# 5G_1.net
KiCad netlist of a schematic drawn in Altium Designer
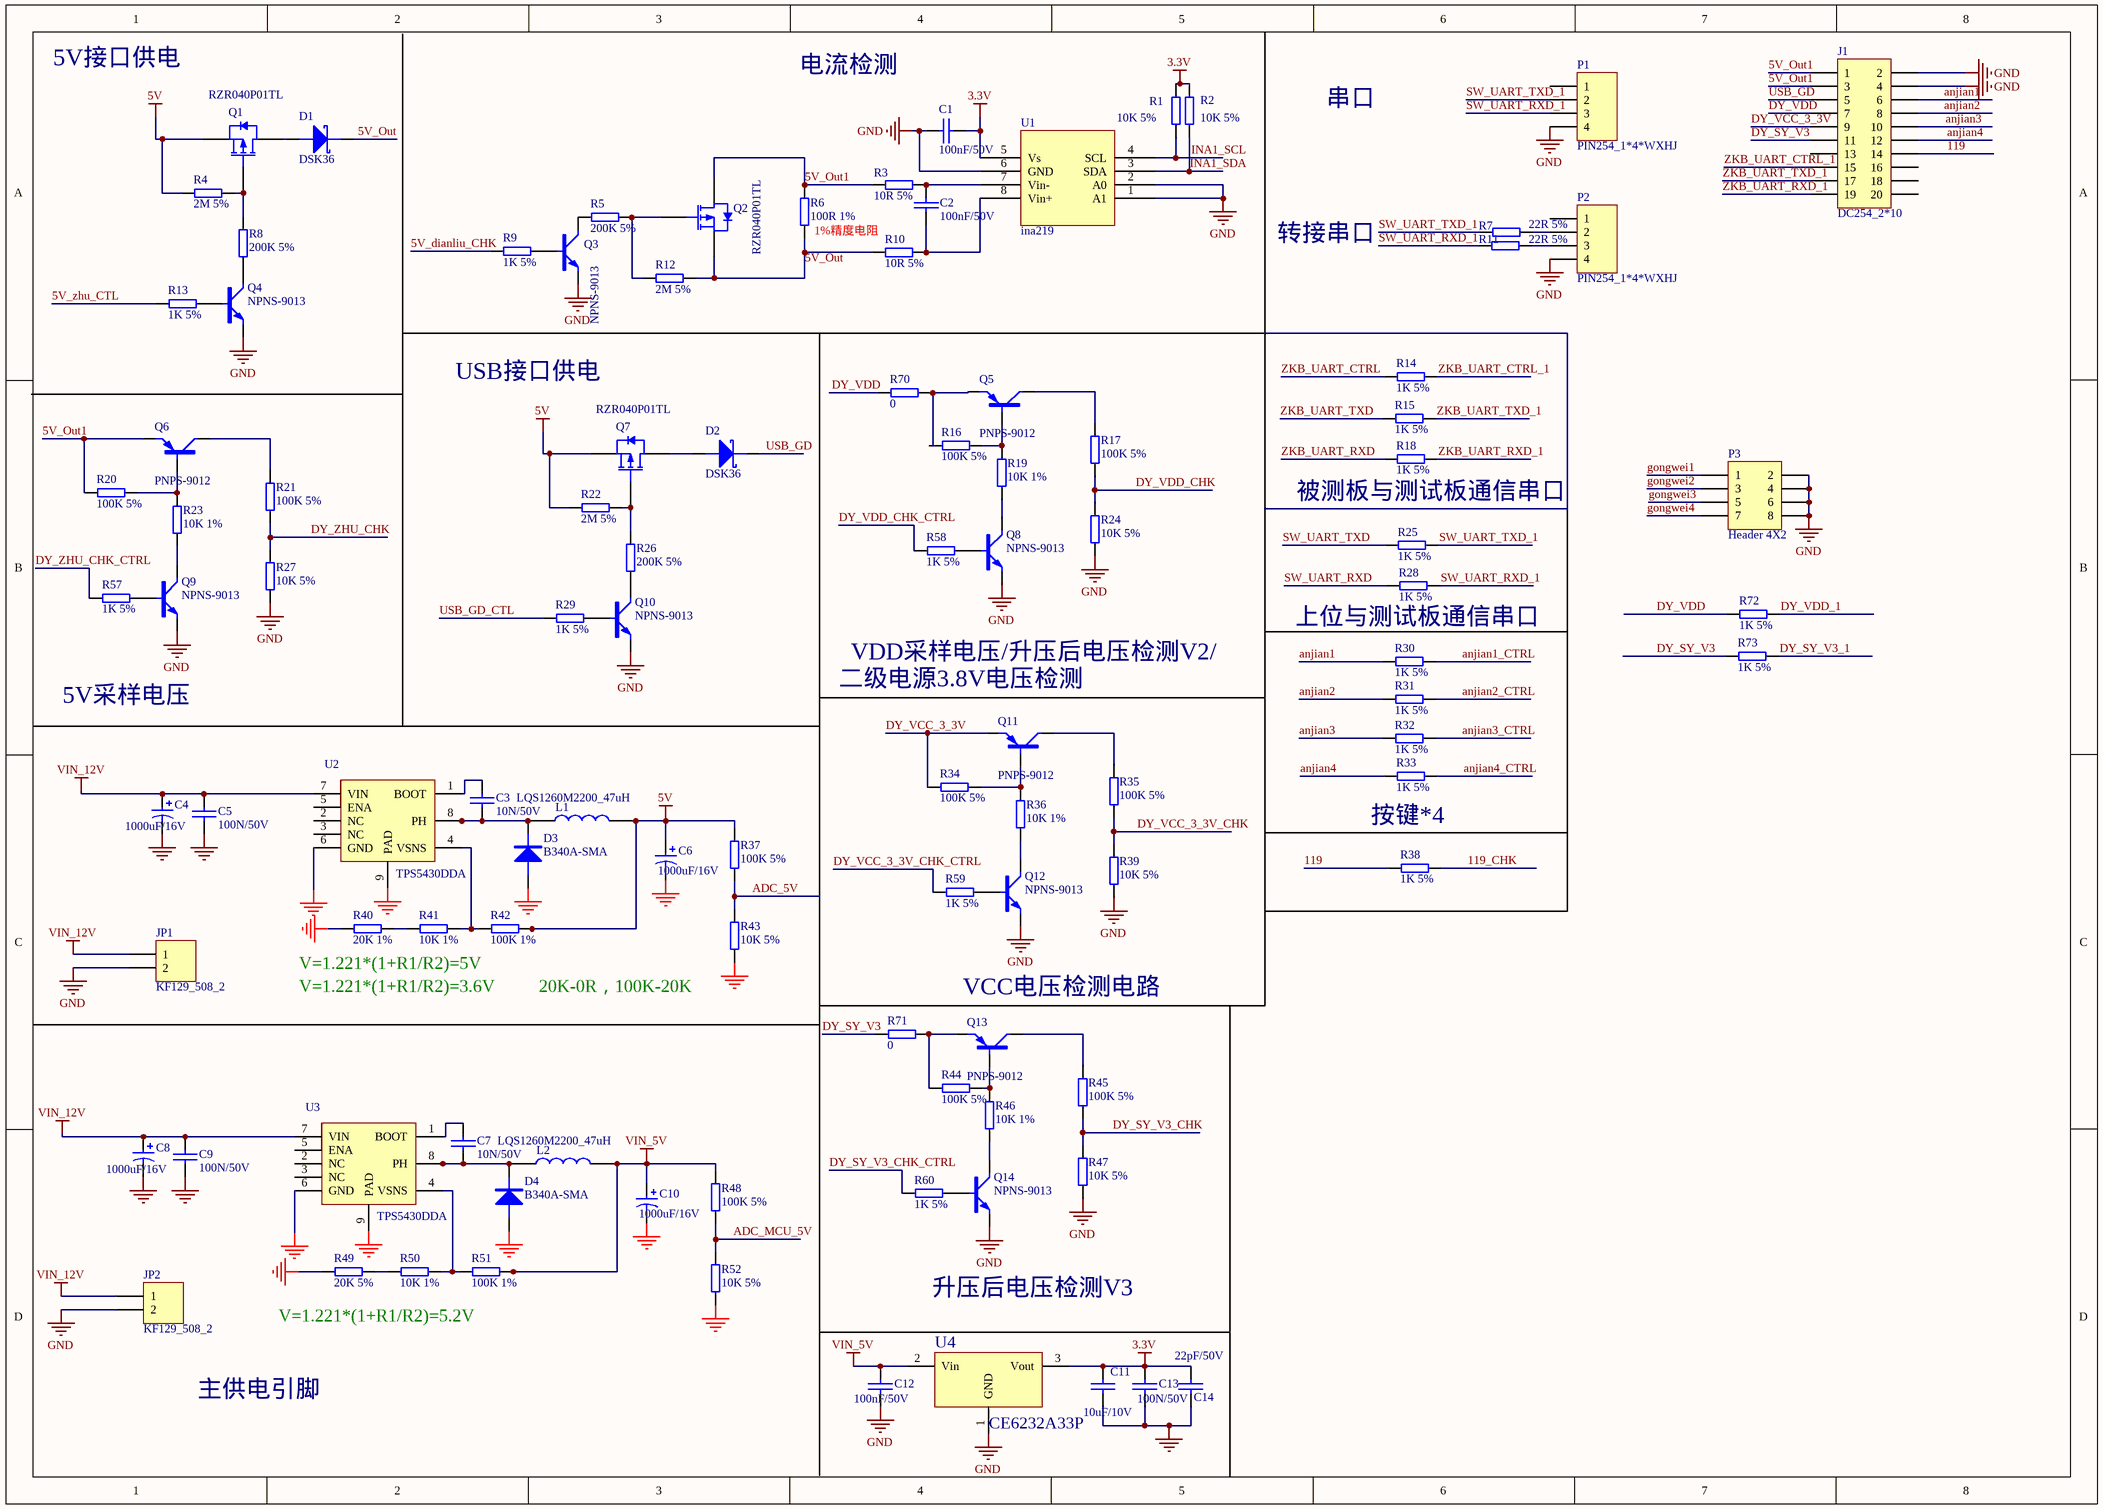
[diagram p0: 5G智慧网关工装1.SchDoc]

(export (version "E")
  (design (tool "Eeschema 10.0.6"))
  (components
    (comp (ref "C1")
      (value "100nF/50V")
      (footprint "CAP0603")
      (description "104pF,50 V,±10%,0603,国巨,CC0603KRX7R9BB104")
      (fields (field (name "PART NUMBER") "101020103-0021"))
      (libsource (lib "Database_Libs2") (part "CC03K7R9_100N"))
    )
    (comp (ref "C2")
      (value "100nF/50V")
      (footprint "CAP0603")
      (description "104pF,50 V,±10%,0603,国巨,CC0603KRX7R9BB104")
      (fields (field (name "PART NUMBER") "101020103-0021"))
      (libsource (lib "Database_Libs2") (part "CC03K7R9_100N"))
    )
    (comp (ref "C3")
      (value "10N/50V")
      (footprint "CAP0603")
      (description "10N/50V，±10%，0603")
      (fields (field (name "PART NUMBER") "101020103-0007"))
      (libsource (lib "Database_Libs1") (part "CC03K7R9B_10N"))
    )
    (comp (ref "C4")
      (value "1000uF/16V")
      (footprint "CAPPC_350_800_1600")
      (description "1000uF,16 V,±20%,8*20mm,Rubycon,16ZLH1000M")
      (fields (field (name "PART NUMBER") "1010203-0029"))
      (libsource (lib "Database_Libs2") (part "CAL7MRZLH_1000U_R"))
    )
    (comp (ref "C5")
      (value "100N/50V")
      (footprint "CAP0603")
      (description "100N/50V，±10%，0603")
      (fields (field (name "PART NUMBER") "101020103-0021"))
      (libsource (lib "Database_Libs1") (part "CC03K7R9B_100N"))
    )
    (comp (ref "C6")
      (value "1000uF/16V")
      (footprint "CAPPC_350_800_1600")
      (description "1000uF,16 V,±20%,8*20mm,Rubycon,16ZLH1000M")
      (fields (field (name "PART NUMBER") "1010203-0029"))
      (libsource (lib "Database_Libs2") (part "CAL7MRZLH_1000U_R"))
    )
    (comp (ref "C7")
      (value "10N/50V")
      (footprint "CAP0603")
      (description "10N/50V，±10%，0603")
      (fields (field (name "PART NUMBER") "101020103-0007"))
      (libsource (lib "Database_Libs1") (part "CC03K7R9B_10N"))
    )
    (comp (ref "C8")
      (value "1000uF/16V")
      (footprint "CAPPC_350_800_1600")
      (description "1000uF,16 V,±20%,8*20mm,Rubycon,16ZLH1000M")
      (fields (field (name "PART NUMBER") "1010203-0029"))
      (libsource (lib "Database_Libs2") (part "CAL7MRZLH_1000U_R"))
    )
    (comp (ref "C9")
      (value "100N/50V")
      (footprint "CAP0603")
      (description "100N/50V，±10%，0603")
      (fields (field (name "PART NUMBER") "101020103-0021"))
      (libsource (lib "Database_Libs1") (part "CC03K7R9B_100N"))
    )
    (comp (ref "C10")
      (value "1000uF/16V")
      (footprint "CAPPC_350_800_1600")
      (description "1000uF,16 V,±20%,8*20mm,Rubycon,16ZLH1000M")
      (fields (field (name "PART NUMBER") "1010203-0029"))
      (libsource (lib "Database_Libs2") (part "CAL7MRZLH_1000U_R"))
    )
    (comp (ref "C11")
      (value "10uF/10V")
      (footprint "CAP0603")
      (description "106pF,10 V,±10%,0603,村田,GRM188R61A106KE47D")
      (fields (field (name "PART NUMBER") "101020103-0026"))
      (libsource (lib "Database_Libs2") (part "CC03K5R6_10U"))
    )
    (comp (ref "C12")
      (value "100nF/50V")
      (footprint "CAP0603")
      (description "104pF,50 V,±10%,0603,国巨,CC0603KRX7R9BB104")
      (fields (field (name "PART NUMBER") "101020103-0021"))
      (libsource (lib "Database_Libs2") (part "CC03K7R9_100N"))
    )
    (comp (ref "C13")
      (value "100N/50V")
      (footprint "CAP0603")
      (description "100N/50V，±10%，0603")
      (fields (field (name "PART NUMBER") "101020103-0021"))
      (libsource (lib "Database_Libs2") (part "CC03K7R9B_100N"))
    )
    (comp (ref "C14")
      (value "22pF/50V")
      (footprint "CAP0603")
      (description "22pF,50 V,±5%,0603,国巨,CC0603JRNPO9BN22")
      (fields (field (name "PART NUMBER") "101020103-0009"))
      (libsource (lib "Database_Libs2") (part "CC03JPO9_22P"))
    )
    (comp (ref "D1")
      (value "DSK36")
      (footprint "SOD-123FL")
      (description "DSK14,SOD-123FL,1 A,40 V,28 V,台湾强茂集团苏州群鑫电子,DSK14")
      (fields (field (name "PART NUMBER") "101040101-0043"))
      (libsource (lib "Database_Libs2") (part "02_DSK14"))
    )
    (comp (ref "D2")
      (value "DSK36")
      (footprint "SOD-123FL")
      (description "DSK14,SOD-123FL,1 A,40 V,28 V,台湾强茂集团苏州群鑫电子,DSK14")
      (fields (field (name "PART NUMBER") "101040101-0043"))
      (libsource (lib "Database_Libs2") (part "02_DSK14"))
    )
    (comp (ref "D3")
      (value "B340A-SMA")
      (footprint "DO-214AC")
      (fields (field (name "PART NUMBER") "101040101-0014"))
      (libsource (lib "Database_Libs1") (part "02_B340A-SMA"))
    )
    (comp (ref "D4")
      (value "B340A-SMA")
      (footprint "DO-214AC")
      (fields (field (name "PART NUMBER") "101040101-0014"))
      (libsource (lib "Database_Libs1") (part "02_B340A-SMA"))
    )
    (comp (ref "J1")
      (value "DC254_2*10")
      (footprint "DC254_2*10")
      (description "DC2 2.54mm 2x10pin,2.54mm间距，2x10pin，32×8.55×27.5mm,母头,双排,双排牛角座")
      (fields (field (name "PART NUMBER") "1010902-0139"))
      (libsource (lib "Database_Libs2") (part "DC254_2*10"))
    )
    (comp (ref "JP1")
      (value "KF129_508_2")
      (footprint "KF129_508_2")
      (description "KF129-2P,螺丝紧固,2,ABS,松涛")
      (fields (field (name "PART NUMBER") "1010904-0015"))
      (libsource (lib "Database_Libs2") (part "KF129_508_2"))
    )
    (comp (ref "JP2")
      (value "KF129_508_2")
      (footprint "KF129_508_2")
      (description "KF129-2P,螺丝紧固,2,ABS,松涛")
      (fields (field (name "PART NUMBER") "1010904-0015"))
      (libsource (lib "Database_Libs2") (part "KF129_508_2"))
    )
    (comp (ref "L1")
      (value "LQS1260M2200_47uH")
      (footprint "LQS1212")
      (description "47uH/2.2A,±20%，0.072Ω，L1200X1200X600")
      (fields (field (name "PART NUMBER") "1010302-0007"))
      (libsource (lib "Database_Libs1") (part "06_LQS1260M2200_47uH"))
    )
    (comp (ref "L2")
      (value "LQS1260M2200_47uH")
      (footprint "LQS1212")
      (description "47uH/2.2A,±20%，0.072Ω，L1200X1200X600")
      (fields (field (name "PART NUMBER") "1010302-0007"))
      (libsource (lib "Database_Libs1") (part "06_LQS1260M2200_47uH"))
    )
    (comp (ref "P1")
      (value "PIN254_1*4*WXHJ")
      (footprint "PIN254_1*4*1100S")
      (description "1*4 ，Φ1.0 ，2.54mm，直脚,无需焊接器件")
      (fields (field (name "PART NUMBER") "AD_WXHJ_PinHeader_01"))
      (libsource (lib "Database_Libs2") (part "PIN254_1*4*1100S"))
    )
    (comp (ref "P2")
      (value "PIN254_1*4*WXHJ")
      (footprint "PIN254_1*4*1100S")
      (description "1*4 ，Φ1.0 ，2.54mm，直脚,无需焊接器件")
      (fields (field (name "PART NUMBER") "AD_WXHJ_PinHeader_01"))
      (libsource (lib "Database_Libs2") (part "PIN254_1*4*1100S"))
    )
    (comp (ref "P3")
      (value "Header 4X2")
      (footprint "HDR2X4")
      (description "Header, 4-Pin, Dual row")
      (libsource (lib "CBB_Lib_SCH") (part "Header 4X2"))
    )
    (comp (ref "Q1")
      (value "RZR040P01TL")
      (footprint "SOT-23")
      (description "RZR040P01TL；1.5v导通,P-MOS,SOT-23,罗姆,RZR040P01TL")
      (fields (field (name "PART NUMBER") "101040201-0010"))
      (libsource (lib "Database_Libs2") (part "03_P-RZR040P01TL"))
    )
    (comp (ref "Q2")
      (value "RZR040P01TL")
      (footprint "SOT-23")
      (description "RZR040P01TL；1.5v导通,P-MOS,SOT-23,罗姆,RZR040P01TL")
      (fields (field (name "PART NUMBER") "101040201-0010"))
      (libsource (lib "Database_Libs2") (part "03_P-RZR040P01TL"))
    )
    (comp (ref "Q3")
      (value "NPNS-9013")
      (footprint "SOT-23")
      (description "9013,NPN,SOT-23,长电,S9013")
      (fields (field (name "PART NUMBER") "101040201-0002"))
      (libsource (lib "Database_Libs2") (part "03_NPNS-9013"))
    )
    (comp (ref "Q4")
      (value "NPNS-9013")
      (footprint "SOT-23")
      (description "9013,NPN,SOT-23,长电,S9013")
      (fields (field (name "PART NUMBER") "101040201-0002"))
      (libsource (lib "Database_Libs2") (part "03_NPNS-9013"))
    )
    (comp (ref "Q5")
      (value "PNPS-9012")
      (footprint "SOT-23")
      (description "9012,PNP,SOT-23,JCET;长电,S9012")
      (fields (field (name "PART NUMBER") "101040201-0001"))
      (libsource (lib "Database_Libs2") (part "03_PNPS-9012"))
    )
    (comp (ref "Q6")
      (value "PNPS-9012")
      (footprint "SOT-23")
      (description "9012,PNP,SOT-23,JCET;长电,S9012")
      (fields (field (name "PART NUMBER") "101040201-0001"))
      (libsource (lib "Database_Libs2") (part "03_PNPS-9012"))
    )
    (comp (ref "Q7")
      (value "RZR040P01TL")
      (footprint "SOT-23")
      (description "RZR040P01TL；1.5v导通,P-MOS,SOT-23,罗姆,RZR040P01TL")
      (fields (field (name "PART NUMBER") "101040201-0010"))
      (libsource (lib "Database_Libs2") (part "03_P-RZR040P01TL"))
    )
    (comp (ref "Q8")
      (value "NPNS-9013")
      (footprint "SOT-23")
      (description "9013,NPN,SOT-23,长电,S9013")
      (fields (field (name "PART NUMBER") "101040201-0002"))
      (libsource (lib "Database_Libs2") (part "03_NPNS-9013"))
    )
    (comp (ref "Q9")
      (value "NPNS-9013")
      (footprint "SOT-23")
      (description "9013,NPN,SOT-23,长电,S9013")
      (fields (field (name "PART NUMBER") "101040201-0002"))
      (libsource (lib "Database_Libs2") (part "03_NPNS-9013"))
    )
    (comp (ref "Q10")
      (value "NPNS-9013")
      (footprint "SOT-23")
      (description "9013,NPN,SOT-23,长电,S9013")
      (fields (field (name "PART NUMBER") "101040201-0002"))
      (libsource (lib "Database_Libs2") (part "03_NPNS-9013"))
    )
    (comp (ref "Q11")
      (value "PNPS-9012")
      (footprint "SOT-23")
      (description "9012,PNP,SOT-23,JCET;长电,S9012")
      (fields (field (name "PART NUMBER") "101040201-0001"))
      (libsource (lib "Database_Libs2") (part "03_PNPS-9012"))
    )
    (comp (ref "Q12")
      (value "NPNS-9013")
      (footprint "SOT-23")
      (description "9013,NPN,SOT-23,长电,S9013")
      (fields (field (name "PART NUMBER") "101040201-0002"))
      (libsource (lib "Database_Libs2") (part "03_NPNS-9013"))
    )
    (comp (ref "Q13")
      (value "PNPS-9012")
      (footprint "SOT-23")
      (description "9012,PNP,SOT-23,JCET;长电,S9012")
      (fields (field (name "PART NUMBER") "101040201-0001"))
      (libsource (lib "Database_Libs2") (part "03_PNPS-9012"))
    )
    (comp (ref "Q14")
      (value "NPNS-9013")
      (footprint "SOT-23")
      (description "9013,NPN,SOT-23,长电,S9013")
      (fields (field (name "PART NUMBER") "101040201-0002"))
      (libsource (lib "Database_Libs2") (part "03_NPNS-9013"))
    )
    (comp (ref "R1")
      (value "10K 5%")
      (footprint "RES0603")
      (description "国巨,±5%,0603,,155 ℃,-55 ℃,RC0603JR-0710KL,无铅,200 ppm/℃,1/10W,,10K")
      (fields (field (name "PART NUMBER") "101010103-0003"))
      (libsource (lib "Database_Libs2") (part "RC03J_10K"))
    )
    (comp (ref "R2")
      (value "10K 5%")
      (footprint "RES0603")
      (description "国巨,±5%,0603,,155 ℃,-55 ℃,RC0603JR-0710KL,无铅,200 ppm/℃,1/10W,,10K")
      (fields (field (name "PART NUMBER") "101010103-0003"))
      (libsource (lib "Database_Libs2") (part "RC03J_10K"))
    )
    (comp (ref "R3")
      (value "10R 5%")
      (footprint "RES0603")
      (description "10R,±5%,1/10W,0603,国巨,RC0603JR-0710RL")
      (fields (field (name "PART NUMBER") "101010103-0017"))
      (libsource (lib "Database_Libs2") (part "RC03J_10R"))
    )
    (comp (ref "R4")
      (value "2M 5%")
      (footprint "RES0603")
      (description "国巨,±5%,0603,,155 ℃,-55 ℃,RC0603JR-072ML,含铅,100 ppm/℃,1/10W,,2M")
      (fields (field (name "PART NUMBER") "101010103-0025"))
      (libsource (lib "Database_Libs2") (part "RC03J_2M"))
    )
    (comp (ref "R5")
      (value "200K 5%")
      (footprint "RES0603")
      (description "200K,±5%,1/10W,0603,国巨,RC0603JR-07200KL")
      (fields (field (name "PART NUMBER") "101010103-0034"))
      (libsource (lib "Database_Libs2") (part "RC03J_200K"))
    )
    (comp (ref "R6")
      (value "100R 1%")
      (footprint "RES0603")
      (description "100Ω,±1%,1/10W,0603,国巨股份有限公司,RC0603FR-07100RL")
      (fields (field (name "PART NUMBER") "101010103-0041"))
      (libsource (lib "Database_Libs2") (part "RC03J_100R"))
    )
    (comp (ref "R7")
      (value "22R 5%")
      (footprint "RES0603")
      (description "国巨,±5%,0603,,155 ℃,-55 ℃,RC0603JR-0722RL,无铅,200 ppm/℃,1/10W,,22欧")
      (fields (field (name "PART NUMBER") "101010103-0009"))
      (libsource (lib "Database_Libs2") (part "RC03J_22R"))
    )
    (comp (ref "R8")
      (value "200K 5%")
      (footprint "RES0603")
      (description "200K,±5%,1/10W,0603,国巨,RC0603JR-07200KL")
      (fields (field (name "PART NUMBER") "101010103-0034"))
      (libsource (lib "Database_Libs2") (part "RC03J_200K"))
    )
    (comp (ref "R9")
      (value "1K 5%")
      (footprint "RES0603")
      (description "1K,±5%,1/10W,0603,国巨,RC0603JR-071KL")
      (fields (field (name "PART NUMBER") "101010103-0008"))
      (libsource (lib "Database_Libs2") (part "RC03J_1K"))
    )
    (comp (ref "R10")
      (value "10R 5%")
      (footprint "RES0603")
      (description "10R,±5%,1/10W,0603,国巨,RC0603JR-0710RL")
      (fields (field (name "PART NUMBER") "101010103-0017"))
      (libsource (lib "Database_Libs2") (part "RC03J_10R"))
    )
    (comp (ref "R11")
      (value "22R 5%")
      (footprint "RES0603")
      (description "国巨,±5%,0603,,155 ℃,-55 ℃,RC0603JR-0722RL,无铅,200 ppm/℃,1/10W,,22欧")
      (fields (field (name "PART NUMBER") "101010103-0009"))
      (libsource (lib "Database_Libs2") (part "RC03J_22R"))
    )
    (comp (ref "R12")
      (value "2M 5%")
      (footprint "RES0603")
      (description "国巨,±5%,0603,,155 ℃,-55 ℃,RC0603JR-072ML,含铅,100 ppm/℃,1/10W,,2M")
      (fields (field (name "PART NUMBER") "101010103-0025"))
      (libsource (lib "Database_Libs2") (part "RC03J_2M"))
    )
    (comp (ref "R13")
      (value "1K 5%")
      (footprint "RES0603")
      (description "1K,±5%,1/10W,0603,国巨,RC0603JR-071KL")
      (fields (field (name "PART NUMBER") "101010103-0008"))
      (libsource (lib "Database_Libs2") (part "RC03J_1K"))
    )
    (comp (ref "R14")
      (value "1K 5%")
      (footprint "RES0603")
      (description "1K,±5%,1/10W,0603,国巨,RC0603JR-071KL")
      (fields (field (name "PART NUMBER") "101010103-0008"))
      (libsource (lib "Database_Libs2") (part "RC03J_1K"))
    )
    (comp (ref "R15")
      (value "1K 5%")
      (footprint "RES0603")
      (description "1K,±5%,1/10W,0603,国巨,RC0603JR-071KL")
      (fields (field (name "PART NUMBER") "101010103-0008"))
      (libsource (lib "Database_Libs2") (part "RC03J_1K"))
    )
    (comp (ref "R16")
      (value "100K 5%")
      (footprint "RES0603")
      (description "国巨,±5%,0603,,155 ℃,-55 ℃,RC0603JR-07100KL,无铅,100 ppm/℃,1/10W,,100K")
      (fields (field (name "PART NUMBER") "101010103-0005"))
      (libsource (lib "Database_Libs2") (part "RC03J_100K"))
    )
    (comp (ref "R17")
      (value "100K 5%")
      (footprint "RES0603")
      (description "国巨,±5%,0603,,155 ℃,-55 ℃,RC0603JR-07100KL,无铅,100 ppm/℃,1/10W,,100K")
      (fields (field (name "PART NUMBER") "101010103-0005"))
      (libsource (lib "Database_Libs2") (part "RC03J_100K"))
    )
    (comp (ref "R18")
      (value "1K 5%")
      (footprint "RES0603")
      (description "1K,±5%,1/10W,0603,国巨,RC0603JR-071KL")
      (fields (field (name "PART NUMBER") "101010103-0008"))
      (libsource (lib "Database_Libs2") (part "RC03J_1K"))
    )
    (comp (ref "R19")
      (value "10K 1%")
      (footprint "RES0603")
      (description "10K±1%,1/10W,0603")
      (fields (field (name "PART NUMBER") "101010103-0052"))
      (libsource (lib "Database_Libs2") (part "RC03J_10K"))
    )
    (comp (ref "R20")
      (value "100K 5%")
      (footprint "RES0603")
      (description "国巨,±5%,0603,,155 ℃,-55 ℃,RC0603JR-07100KL,无铅,100 ppm/℃,1/10W,,100K")
      (fields (field (name "PART NUMBER") "101010103-0005"))
      (libsource (lib "Database_Libs2") (part "RC03J_100K"))
    )
    (comp (ref "R21")
      (value "100K 5%")
      (footprint "RES0603")
      (description "国巨,±5%,0603,,155 ℃,-55 ℃,RC0603JR-07100KL,无铅,100 ppm/℃,1/10W,,100K")
      (fields (field (name "PART NUMBER") "101010103-0005"))
      (libsource (lib "Database_Libs2") (part "RC03J_100K"))
    )
    (comp (ref "R22")
      (value "2M 5%")
      (footprint "RES0603")
      (description "国巨,±5%,0603,,155 ℃,-55 ℃,RC0603JR-072ML,含铅,100 ppm/℃,1/10W,,2M")
      (fields (field (name "PART NUMBER") "101010103-0025"))
      (libsource (lib "Database_Libs2") (part "RC03J_2M"))
    )
    (comp (ref "R23")
      (value "10K 1%")
      (footprint "RES0603")
      (description "10K±1%,1/10W,0603")
      (fields (field (name "PART NUMBER") "101010103-0052"))
      (libsource (lib "Database_Libs2") (part "RC03J_10K"))
    )
    (comp (ref "R24")
      (value "10K 5%")
      (footprint "RES0603")
      (description "国巨,±5%,0603,,155 ℃,-55 ℃,RC0603JR-0710KL,无铅,200 ppm/℃,1/10W,,10K")
      (fields (field (name "PART NUMBER") "101010103-0003"))
      (libsource (lib "Database_Libs2") (part "RC03J_10K"))
    )
    (comp (ref "R25")
      (value "1K 5%")
      (footprint "RES0603")
      (description "1K,±5%,1/10W,0603,国巨,RC0603JR-071KL")
      (fields (field (name "PART NUMBER") "101010103-0008"))
      (libsource (lib "Database_Libs2") (part "RC03J_1K"))
    )
    (comp (ref "R26")
      (value "200K 5%")
      (footprint "RES0603")
      (description "200K,±5%,1/10W,0603,国巨,RC0603JR-07200KL")
      (fields (field (name "PART NUMBER") "101010103-0034"))
      (libsource (lib "Database_Libs2") (part "RC03J_200K"))
    )
    (comp (ref "R27")
      (value "10K 5%")
      (footprint "RES0603")
      (description "国巨,±5%,0603,,155 ℃,-55 ℃,RC0603JR-0710KL,无铅,200 ppm/℃,1/10W,,10K")
      (fields (field (name "PART NUMBER") "101010103-0003"))
      (libsource (lib "Database_Libs2") (part "RC03J_10K"))
    )
    (comp (ref "R28")
      (value "1K 5%")
      (footprint "RES0603")
      (description "1K,±5%,1/10W,0603,国巨,RC0603JR-071KL")
      (fields (field (name "PART NUMBER") "101010103-0008"))
      (libsource (lib "Database_Libs2") (part "RC03J_1K"))
    )
    (comp (ref "R29")
      (value "1K 5%")
      (footprint "RES0603")
      (description "1K,±5%,1/10W,0603,国巨,RC0603JR-071KL")
      (fields (field (name "PART NUMBER") "101010103-0008"))
      (libsource (lib "Database_Libs2") (part "RC03J_1K"))
    )
    (comp (ref "R30")
      (value "1K 5%")
      (footprint "RES0603")
      (description "1K,±5%,1/10W,0603,国巨,RC0603JR-071KL")
      (fields (field (name "PART NUMBER") "101010103-0008"))
      (libsource (lib "Database_Libs2") (part "RC03J_1K"))
    )
    (comp (ref "R31")
      (value "1K 5%")
      (footprint "RES0603")
      (description "1K,±5%,1/10W,0603,国巨,RC0603JR-071KL")
      (fields (field (name "PART NUMBER") "101010103-0008"))
      (libsource (lib "Database_Libs2") (part "RC03J_1K"))
    )
    (comp (ref "R32")
      (value "1K 5%")
      (footprint "RES0603")
      (description "1K,±5%,1/10W,0603,国巨,RC0603JR-071KL")
      (fields (field (name "PART NUMBER") "101010103-0008"))
      (libsource (lib "Database_Libs2") (part "RC03J_1K"))
    )
    (comp (ref "R33")
      (value "1K 5%")
      (footprint "RES0603")
      (description "1K,±5%,1/10W,0603,国巨,RC0603JR-071KL")
      (fields (field (name "PART NUMBER") "101010103-0008"))
      (libsource (lib "Database_Libs2") (part "RC03J_1K"))
    )
    (comp (ref "R34")
      (value "100K 5%")
      (footprint "RES0603")
      (description "国巨,±5%,0603,,155 ℃,-55 ℃,RC0603JR-07100KL,无铅,100 ppm/℃,1/10W,,100K")
      (fields (field (name "PART NUMBER") "101010103-0005"))
      (libsource (lib "Database_Libs2") (part "RC03J_100K"))
    )
    (comp (ref "R35")
      (value "100K 5%")
      (footprint "RES0603")
      (description "国巨,±5%,0603,,155 ℃,-55 ℃,RC0603JR-07100KL,无铅,100 ppm/℃,1/10W,,100K")
      (fields (field (name "PART NUMBER") "101010103-0005"))
      (libsource (lib "Database_Libs2") (part "RC03J_100K"))
    )
    (comp (ref "R36")
      (value "10K 1%")
      (footprint "RES0603")
      (description "10K±1%,1/10W,0603")
      (fields (field (name "PART NUMBER") "101010103-0052"))
      (libsource (lib "Database_Libs2") (part "RC03J_10K"))
    )
    (comp (ref "R37")
      (value "100K 5%")
      (footprint "RES0603")
      (description "100K±5%,1/10W,0603")
      (fields (field (name "PART NUMBER") "101010103-0005"))
      (libsource (lib "Database_Libs1") (part "RC03JF_100K"))
    )
    (comp (ref "R38")
      (value "1K 5%")
      (footprint "RES0603")
      (description "1K,±5%,1/10W,0603,国巨,RC0603JR-071KL")
      (fields (field (name "PART NUMBER") "101010103-0008"))
      (libsource (lib "Database_Libs2") (part "RC03J_1K"))
    )
    (comp (ref "R39")
      (value "10K 5%")
      (footprint "RES0603")
      (description "国巨,±5%,0603,,155 ℃,-55 ℃,RC0603JR-0710KL,无铅,200 ppm/℃,1/10W,,10K")
      (fields (field (name "PART NUMBER") "101010103-0003"))
      (libsource (lib "Database_Libs2") (part "RC03J_10K"))
    )
    (comp (ref "R40")
      (value "20K 1%")
      (footprint "RES0603")
      (description "20K,±1%,1/10W,0603,国巨,RC0603FR-0720KL")
      (fields (field (name "PART NUMBER") "101010103-0048"))
      (libsource (lib "Database_Libs2") (part "RC03J_20K"))
    )
    (comp (ref "R41")
      (value "10K 1%")
      (footprint "RES0603")
      (description "8.2k±1%,1/10W,0603")
      (fields (field (name "PART NUMBER") "101010103-0053"))
      (libsource (lib "Database_Libs1") (part "RC03FF_8.2K"))
    )
    (comp (ref "R42")
      (value "100K 1%")
      (footprint "RES0603")
      (description "20K±1%,1/10W,0603")
      (fields (field (name "PART NUMBER") "101010103-0048"))
      (libsource (lib "Database_Libs1") (part "RC03FF_20K"))
    )
    (comp (ref "R43")
      (value "10K 5%")
      (footprint "RES0603")
      (description "100K±5%,1/10W,0603")
      (fields (field (name "PART NUMBER") "101010103-0005"))
      (libsource (lib "Database_Libs1") (part "RC03JF_100K"))
    )
    (comp (ref "R44")
      (value "100K 5%")
      (footprint "RES0603")
      (description "国巨,±5%,0603,,155 ℃,-55 ℃,RC0603JR-07100KL,无铅,100 ppm/℃,1/10W,,100K")
      (fields (field (name "PART NUMBER") "101010103-0005"))
      (libsource (lib "Database_Libs2") (part "RC03J_100K"))
    )
    (comp (ref "R45")
      (value "100K 5%")
      (footprint "RES0603")
      (description "国巨,±5%,0603,,155 ℃,-55 ℃,RC0603JR-07100KL,无铅,100 ppm/℃,1/10W,,100K")
      (fields (field (name "PART NUMBER") "101010103-0005"))
      (libsource (lib "Database_Libs2") (part "RC03J_100K"))
    )
    (comp (ref "R46")
      (value "10K 1%")
      (footprint "RES0603")
      (description "10K±1%,1/10W,0603")
      (fields (field (name "PART NUMBER") "101010103-0052"))
      (libsource (lib "Database_Libs2") (part "RC03J_10K"))
    )
    (comp (ref "R47")
      (value "10K 5%")
      (footprint "RES0603")
      (description "国巨,±5%,0603,,155 ℃,-55 ℃,RC0603JR-0710KL,无铅,200 ppm/℃,1/10W,,10K")
      (fields (field (name "PART NUMBER") "101010103-0003"))
      (libsource (lib "Database_Libs2") (part "RC03J_10K"))
    )
    (comp (ref "R48")
      (value "100K 5%")
      (footprint "RES0603")
      (description "100K±5%,1/10W,0603")
      (fields (field (name "PART NUMBER") "101010103-0005"))
      (libsource (lib "Database_Libs1") (part "RC03JF_100K"))
    )
    (comp (ref "R49")
      (value "20K 5%")
      (footprint "RES0603")
      (description "国巨,±5%,0603,,155 ℃,-55 ℃,RC0603JR-0720KL,无铅,200 ppm/℃,1/10W,,20K")
      (fields (field (name "PART NUMBER") "101010103-0004"))
      (libsource (lib "Database_Libs2") (part "RC03J_20K"))
    )
    (comp (ref "R50")
      (value "10K 1%")
      (footprint "RES0603")
      (description "8.2k±1%,1/10W,0603")
      (fields (field (name "PART NUMBER") "101010103-0053"))
      (libsource (lib "Database_Libs1") (part "RC03FF_8.2K"))
    )
    (comp (ref "R51")
      (value "100K 1%")
      (footprint "RES0603")
      (description "20K±1%,1/10W,0603")
      (fields (field (name "PART NUMBER") "101010103-0048"))
      (libsource (lib "Database_Libs1") (part "RC03FF_20K"))
    )
    (comp (ref "R52")
      (value "10K 5%")
      (footprint "RES0603")
      (description "100K±5%,1/10W,0603")
      (fields (field (name "PART NUMBER") "101010103-0005"))
      (libsource (lib "Database_Libs1") (part "RC03JF_100K"))
    )
    (comp (ref "R57")
      (value "1K 5%")
      (footprint "RES0603")
      (description "1K,±5%,1/10W,0603,国巨,RC0603JR-071KL")
      (fields (field (name "PART NUMBER") "101010103-0008"))
      (libsource (lib "Database_Libs2") (part "RC03J_1K"))
    )
    (comp (ref "R58")
      (value "1K 5%")
      (footprint "RES0603")
      (description "1K,±5%,1/10W,0603,国巨,RC0603JR-071KL")
      (fields (field (name "PART NUMBER") "101010103-0008"))
      (libsource (lib "Database_Libs2") (part "RC03J_1K"))
    )
    (comp (ref "R59")
      (value "1K 5%")
      (footprint "RES0603")
      (description "1K,±5%,1/10W,0603,国巨,RC0603JR-071KL")
      (fields (field (name "PART NUMBER") "101010103-0008"))
      (libsource (lib "Database_Libs2") (part "RC03J_1K"))
    )
    (comp (ref "R60")
      (value "1K 5%")
      (footprint "RES0603")
      (description "1K,±5%,1/10W,0603,国巨,RC0603JR-071KL")
      (fields (field (name "PART NUMBER") "101010103-0008"))
      (libsource (lib "Database_Libs2") (part "RC03J_1K"))
    )
    (comp (ref "R70")
      (value "0")
      (footprint "RES0603")
      (description "国巨,±5%,0603,,155 ℃,-55 ℃,RC0603JR-07100KL,无铅,100 ppm/℃,1/10W,,100K")
      (fields (field (name "PART NUMBER") "101010103-0005"))
      (libsource (lib "Database_Libs2") (part "RC03J_100K"))
    )
    (comp (ref "R71")
      (value "0")
      (footprint "RES0603")
      (description "国巨,±5%,0603,,155 ℃,-55 ℃,RC0603JR-07100KL,无铅,100 ppm/℃,1/10W,,100K")
      (fields (field (name "PART NUMBER") "101010103-0005"))
      (libsource (lib "Database_Libs2") (part "RC03J_100K"))
    )
    (comp (ref "R72")
      (value "1K 5%")
      (footprint "RES0603")
      (description "1K,±5%,1/10W,0603,国巨,RC0603JR-071KL")
      (fields (field (name "PART NUMBER") "101010103-0008"))
      (libsource (lib "Database_Libs2") (part "RC03J_1K"))
    )
    (comp (ref "R73")
      (value "1K 5%")
      (footprint "RES0603")
      (description "1K,±5%,1/10W,0603,国巨,RC0603JR-071KL")
      (fields (field (name "PART NUMBER") "101010103-0008"))
      (libsource (lib "Database_Libs2") (part "RC03J_1K"))
    )
    (comp (ref "U1") (value "ina219") (footprint "SO-8") (libsource (lib "Schlib1") (part "Component_2")))
    (comp (ref "U2")
      (value "TPS5430DDA")
      (footprint "SOP-8-P")
      (description "TPS5430DDA,SOP8,TI,TPS5430DDA")
      (fields (field (name "PART NUMBER") "101050101-0053"))
      (libsource (lib "Database_Libs2") (part "02_TPS5430DDA"))
    )
    (comp (ref "U3")
      (value "TPS5430DDA")
      (footprint "SOP-8-P")
      (description "TPS5430DDA,SOP8,TI,TPS5430DDA")
      (fields (field (name "PART NUMBER") "101050101-0053"))
      (libsource (lib "Database_Libs2") (part "02_TPS5430DDA"))
    )
    (comp (ref "U4")
      (value "CE6232A33P")
      (footprint "SOT-89")
      (description "CE6232-3.3,CE6232-3.3,SOT89-3,8V,1.8V,0.11V,3.3V,300mA,0.8uA,南京芯力微电子有限公司")
      (fields (field (name "PART NUMBER") "1010503-0029"))
      (libsource (lib "Database_Libs2") (part "02_CE6232A33P"))
    )
  )
  (nets
    (net (code "1") (name "/5V_Out") (class "Default")
      (node (ref "D1") (pin "2") (pinfunction "2_2") (pintype "passive"))
      (node (ref "Q2") (pin "2") (pinfunction "S_2") (pintype "passive"))
      (node (ref "R10") (pin "1") (pinfunction "1_1") (pintype "passive"))
      (node (ref "R12") (pin "2") (pinfunction "2_2") (pintype "passive"))
      (node (ref "R6") (pin "1") (pinfunction "1_1") (pintype "passive"))
    )
    (net (code "2") (name "/5V_Out1") (class "Default")
      (node (ref "J1") (pin "1") (pinfunction "1_1") (pintype "passive"))
      (node (ref "J1") (pin "3") (pinfunction "3_3") (pintype "passive"))
      (node (ref "Q2") (pin "3") (pinfunction "D_3") (pintype "passive"))
      (node (ref "Q6") (pin "2") (pinfunction "E_2") (pintype "passive"))
      (node (ref "R20") (pin "2") (pinfunction "2_2") (pintype "passive"))
      (node (ref "R3") (pin "1") (pinfunction "1_1") (pintype "passive"))
      (node (ref "R6") (pin "2") (pinfunction "2_2") (pintype "passive"))
    )
    (net (code "3") (name "/5V_dianliu_CHK") (class "Default")
      (node (ref "R9") (pin "2") (pinfunction "2_2") (pintype "passive"))
    )
    (net (code "4") (name "/5V_zhu_CTL") (class "Default")
      (node (ref "R13") (pin "1") (pinfunction "1_1") (pintype "passive"))
    )
    (net (code "5") (name "/119") (class "Default")
      (node (ref "J1") (pin "14") (pinfunction "14_14") (pintype "passive"))
      (node (ref "R38") (pin "1") (pinfunction "1_1") (pintype "passive"))
    )
    (net (code "6") (name "/119_CHK") (class "Default")
      (node (ref "R38") (pin "2") (pinfunction "2_2") (pintype "passive"))
    )
    (net (code "7") (name "/ADC_5V") (class "Default")
      (node (ref "R37") (pin "1") (pinfunction "1_1") (pintype "passive"))
      (node (ref "R43") (pin "2") (pinfunction "2_2") (pintype "passive"))
    )
    (net (code "8") (name "/ADC_MCU_5V") (class "Default")
      (node (ref "R48") (pin "1") (pinfunction "1_1") (pintype "passive"))
      (node (ref "R52") (pin "2") (pinfunction "2_2") (pintype "passive"))
    )
    (net (code "9") (name "/DY_SY_V3") (class "Default")
      (node (ref "J1") (pin "11") (pinfunction "11_11") (pintype "passive"))
      (node (ref "R71") (pin "2") (pinfunction "2_2") (pintype "passive"))
      (node (ref "R73") (pin "1") (pinfunction "1_1") (pintype "passive"))
    )
    (net (code "10") (name "/DY_SY_V3_1") (class "Default")
      (node (ref "R73") (pin "2") (pinfunction "2_2") (pintype "passive"))
    )
    (net (code "11") (name "/DY_SY_V3_CHK") (class "Default")
      (node (ref "R45") (pin "2") (pinfunction "2_2") (pintype "passive"))
      (node (ref "R47") (pin "1") (pinfunction "1_1") (pintype "passive"))
    )
    (net (code "12") (name "/DY_SY_V3_CHK_CTRL") (class "Default")
      (node (ref "R60") (pin "1") (pinfunction "1_1") (pintype "passive"))
    )
    (net (code "13") (name "/DY_VCC_3_3V") (class "Default")
      (node (ref "J1") (pin "9") (pinfunction "9_9") (pintype "passive"))
      (node (ref "Q11") (pin "2") (pinfunction "E_2") (pintype "passive"))
      (node (ref "R34") (pin "2") (pinfunction "2_2") (pintype "passive"))
    )
    (net (code "14") (name "/DY_VCC_3_3V_CHK") (class "Default")
      (node (ref "R35") (pin "2") (pinfunction "2_2") (pintype "passive"))
      (node (ref "R39") (pin "1") (pinfunction "1_1") (pintype "passive"))
    )
    (net (code "15") (name "/DY_VCC_3_3V_CHK_CTRL") (class "Default")
      (node (ref "R59") (pin "1") (pinfunction "1_1") (pintype "passive"))
    )
    (net (code "16") (name "/DY_VDD") (class "Default")
      (node (ref "J1") (pin "7") (pinfunction "7_7") (pintype "passive"))
      (node (ref "R70") (pin "2") (pinfunction "2_2") (pintype "passive"))
      (node (ref "R72") (pin "1") (pinfunction "1_1") (pintype "passive"))
    )
    (net (code "17") (name "/DY_VDD_1") (class "Default")
      (node (ref "R72") (pin "2") (pinfunction "2_2") (pintype "passive"))
    )
    (net (code "18") (name "/DY_VDD_CHK") (class "Default")
      (node (ref "R17") (pin "2") (pinfunction "2_2") (pintype "passive"))
      (node (ref "R24") (pin "1") (pinfunction "1_1") (pintype "passive"))
    )
    (net (code "19") (name "/DY_VDD_CHK_CTRL") (class "Default")
      (node (ref "R58") (pin "1") (pinfunction "1_1") (pintype "passive"))
    )
    (net (code "20") (name "/DY_ZHU_CHK") (class "Default")
      (node (ref "R21") (pin "2") (pinfunction "2_2") (pintype "passive"))
      (node (ref "R27") (pin "1") (pinfunction "1_1") (pintype "passive"))
    )
    (net (code "21") (name "/DY_ZHU_CHK_CTRL") (class "Default")
      (node (ref "R57") (pin "1") (pinfunction "1_1") (pintype "passive"))
    )
    (net (code "22") (name "/INA1_SCL") (class "Default")
      (node (ref "R1") (pin "2") (pinfunction "2_2") (pintype "passive"))
      (node (ref "U1") (pin "4") (pinfunction "SCL_4") (pintype "passive"))
    )
    (net (code "23") (name "/INA1_SDA") (class "Default")
      (node (ref "R2") (pin "2") (pinfunction "2_2") (pintype "passive"))
      (node (ref "U1") (pin "3") (pinfunction "SDA_3") (pintype "passive"))
    )
    (net (code "24") (name "/SW_UART_RXD") (class "Default")
      (node (ref "R28") (pin "1") (pinfunction "1_1") (pintype "passive"))
    )
    (net (code "25") (name "/SW_UART_RXD_1") (class "Default")
      (node (ref "P1") (pin "3") (pinfunction "3_3") (pintype "passive"))
      (node (ref "R11") (pin "1") (pinfunction "1_1") (pintype "passive"))
      (node (ref "R28") (pin "2") (pinfunction "2_2") (pintype "passive"))
    )
    (net (code "26") (name "/SW_UART_TXD") (class "Default")
      (node (ref "R25") (pin "1") (pinfunction "1_1") (pintype "passive"))
    )
    (net (code "27") (name "/SW_UART_TXD_1") (class "Default")
      (node (ref "P1") (pin "2") (pinfunction "2_2") (pintype "passive"))
      (node (ref "R25") (pin "2") (pinfunction "2_2") (pintype "passive"))
      (node (ref "R7") (pin "1") (pinfunction "1_1") (pintype "passive"))
    )
    (net (code "28") (name "/USB_GD") (class "Default")
      (node (ref "D2") (pin "2") (pinfunction "2_2") (pintype "passive"))
      (node (ref "J1") (pin "5") (pinfunction "5_5") (pintype "passive"))
    )
    (net (code "29") (name "/USB_GD_CTL") (class "Default")
      (node (ref "R29") (pin "1") (pinfunction "1_1") (pintype "passive"))
    )
    (net (code "30") (name "/ZKB_UART_CTRL") (class "Default")
      (node (ref "R14") (pin "1") (pinfunction "1_1") (pintype "passive"))
    )
    (net (code "31") (name "/ZKB_UART_CTRL_1") (class "Default")
      (node (ref "J1") (pin "15") (pinfunction "15_15") (pintype "passive"))
      (node (ref "R14") (pin "2") (pinfunction "2_2") (pintype "passive"))
    )
    (net (code "32") (name "/ZKB_UART_RXD") (class "Default")
      (node (ref "R18") (pin "1") (pinfunction "1_1") (pintype "passive"))
    )
    (net (code "33") (name "/ZKB_UART_RXD_1") (class "Default")
      (node (ref "J1") (pin "19") (pinfunction "19_19") (pintype "passive"))
      (node (ref "R18") (pin "2") (pinfunction "2_2") (pintype "passive"))
    )
    (net (code "34") (name "/ZKB_UART_TXD") (class "Default")
      (node (ref "R15") (pin "1") (pinfunction "1_1") (pintype "passive"))
    )
    (net (code "35") (name "/ZKB_UART_TXD_1") (class "Default")
      (node (ref "J1") (pin "17") (pinfunction "17_17") (pintype "passive"))
      (node (ref "R15") (pin "2") (pinfunction "2_2") (pintype "passive"))
    )
    (net (code "36") (name "/anjian1") (class "Default")
      (node (ref "J1") (pin "6") (pinfunction "6_6") (pintype "passive"))
      (node (ref "R30") (pin "1") (pinfunction "1_1") (pintype "passive"))
    )
    (net (code "37") (name "/anjian1_CTRL") (class "Default")
      (node (ref "R30") (pin "2") (pinfunction "2_2") (pintype "passive"))
    )
    (net (code "38") (name "/anjian2") (class "Default")
      (node (ref "J1") (pin "8") (pinfunction "8_8") (pintype "passive"))
      (node (ref "R31") (pin "1") (pinfunction "1_1") (pintype "passive"))
    )
    (net (code "39") (name "/anjian2_CTRL") (class "Default")
      (node (ref "R31") (pin "2") (pinfunction "2_2") (pintype "passive"))
    )
    (net (code "40") (name "/anjian3") (class "Default")
      (node (ref "J1") (pin "10") (pinfunction "10_10") (pintype "passive"))
      (node (ref "R32") (pin "1") (pinfunction "1_1") (pintype "passive"))
    )
    (net (code "41") (name "/anjian3_CTRL") (class "Default")
      (node (ref "R32") (pin "2") (pinfunction "2_2") (pintype "passive"))
    )
    (net (code "42") (name "/anjian4") (class "Default")
      (node (ref "J1") (pin "12") (pinfunction "12_12") (pintype "passive"))
      (node (ref "R33") (pin "1") (pinfunction "1_1") (pintype "passive"))
    )
    (net (code "43") (name "/anjian4_CTRL") (class "Default")
      (node (ref "R33") (pin "2") (pinfunction "2_2") (pintype "passive"))
    )
    (net (code "44") (name "/gongwei1") (class "Default")
      (node (ref "P3") (pin "1") (pinfunction "1_1") (pintype "passive"))
    )
    (net (code "45") (name "/gongwei2") (class "Default")
      (node (ref "P3") (pin "3") (pinfunction "3_3") (pintype "passive"))
    )
    (net (code "46") (name "/gongwei3") (class "Default")
      (node (ref "P3") (pin "5") (pinfunction "5_5") (pintype "passive"))
    )
    (net (code "47") (name "/gongwei4") (class "Default")
      (node (ref "P3") (pin "7") (pinfunction "7_7") (pintype "passive"))
    )
    (net (code "48") (name "3.3V") (class "Default")
      (node (ref "C1") (pin "2") (pinfunction "2_2") (pintype "passive"))
      (node (ref "C11") (pin "1") (pinfunction "1_1") (pintype "passive"))
      (node (ref "C13") (pin "1") (pinfunction "1_1") (pintype "passive"))
      (node (ref "C14") (pin "1") (pinfunction "1_1") (pintype "passive"))
      (node (ref "R1") (pin "1") (pinfunction "1_1") (pintype "passive"))
      (node (ref "R2") (pin "1") (pinfunction "1_1") (pintype "passive"))
      (node (ref "U1") (pin "5") (pinfunction "Vs_5") (pintype "passive"))
      (node (ref "U4") (pin "3") (pinfunction "Vout_3") (pintype "passive"))
    )
    (net (code "49") (name "5V") (class "Default")
      (node (ref "C6") (pin "1") (pinfunction "1_1") (pintype "passive"))
      (node (ref "L1") (pin "2") (pinfunction "2_2") (pintype "passive"))
      (node (ref "Q1") (pin "2") (pinfunction "S_2") (pintype "passive"))
      (node (ref "Q7") (pin "2") (pinfunction "S_2") (pintype "passive"))
      (node (ref "R22") (pin "1") (pinfunction "1_1") (pintype "passive"))
      (node (ref "R37") (pin "2") (pinfunction "2_2") (pintype "passive"))
      (node (ref "R4") (pin "1") (pinfunction "1_1") (pintype "passive"))
      (node (ref "R42") (pin "2") (pinfunction "2_2") (pintype "passive"))
    )
    (net (code "50") (name "GND") (class "Default")
      (node (ref "C1") (pin "1") (pinfunction "1_1") (pintype "passive"))
      (node (ref "C10") (pin "2") (pinfunction "2_2") (pintype "passive"))
      (node (ref "C11") (pin "2") (pinfunction "2_2") (pintype "passive"))
      (node (ref "C12") (pin "2") (pinfunction "2_2") (pintype "passive"))
      (node (ref "C13") (pin "2") (pinfunction "2_2") (pintype "passive"))
      (node (ref "C14") (pin "2") (pinfunction "2_2") (pintype "passive"))
      (node (ref "C4") (pin "2") (pinfunction "2_2") (pintype "passive"))
      (node (ref "C5") (pin "2") (pinfunction "2_2") (pintype "passive"))
      (node (ref "C6") (pin "2") (pinfunction "2_2") (pintype "passive"))
      (node (ref "C8") (pin "2") (pinfunction "2_2") (pintype "passive"))
      (node (ref "C9") (pin "2") (pinfunction "2_2") (pintype "passive"))
      (node (ref "D3") (pin "1") (pinfunction "1_1") (pintype "passive"))
      (node (ref "D4") (pin "1") (pinfunction "1_1") (pintype "passive"))
      (node (ref "J1") (pin "2") (pinfunction "2_2") (pintype "passive"))
      (node (ref "J1") (pin "4") (pinfunction "4_4") (pintype "passive"))
      (node (ref "JP1") (pin "2") (pinfunction "2_2") (pintype "passive"))
      (node (ref "JP2") (pin "2") (pinfunction "2_2") (pintype "passive"))
      (node (ref "P1") (pin "4") (pinfunction "4_4") (pintype "passive"))
      (node (ref "P2") (pin "4") (pinfunction "4_4") (pintype "passive"))
      (node (ref "P3") (pin "2") (pinfunction "2_2") (pintype "passive"))
      (node (ref "P3") (pin "4") (pinfunction "4_4") (pintype "passive"))
      (node (ref "P3") (pin "6") (pinfunction "6_6") (pintype "passive"))
      (node (ref "P3") (pin "8") (pinfunction "8_8") (pintype "passive"))
      (node (ref "Q10") (pin "2") (pinfunction "E_2") (pintype "passive"))
      (node (ref "Q12") (pin "2") (pinfunction "E_2") (pintype "passive"))
      (node (ref "Q14") (pin "2") (pinfunction "E_2") (pintype "passive"))
      (node (ref "Q3") (pin "2") (pinfunction "E_2") (pintype "passive"))
      (node (ref "Q4") (pin "2") (pinfunction "E_2") (pintype "passive"))
      (node (ref "Q8") (pin "2") (pinfunction "E_2") (pintype "passive"))
      (node (ref "Q9") (pin "2") (pinfunction "E_2") (pintype "passive"))
      (node (ref "R24") (pin "2") (pinfunction "2_2") (pintype "passive"))
      (node (ref "R27") (pin "2") (pinfunction "2_2") (pintype "passive"))
      (node (ref "R39") (pin "2") (pinfunction "2_2") (pintype "passive"))
      (node (ref "R40") (pin "1") (pinfunction "1_1") (pintype "passive"))
      (node (ref "R43") (pin "1") (pinfunction "1_1") (pintype "passive"))
      (node (ref "R47") (pin "2") (pinfunction "2_2") (pintype "passive"))
      (node (ref "R49") (pin "1") (pinfunction "1_1") (pintype "passive"))
      (node (ref "R52") (pin "1") (pinfunction "1_1") (pintype "passive"))
      (node (ref "U1") (pin "1") (pinfunction "A1_1") (pintype "passive"))
      (node (ref "U1") (pin "2") (pinfunction "A0_2") (pintype "passive"))
      (node (ref "U1") (pin "6") (pinfunction "GND_6") (pintype "passive"))
      (node (ref "U2") (pin "6") (pinfunction "GND_6") (pintype "passive"))
      (node (ref "U2") (pin "9") (pinfunction "PAD_9") (pintype "passive"))
      (node (ref "U3") (pin "6") (pinfunction "GND_6") (pintype "passive"))
      (node (ref "U3") (pin "9") (pinfunction "PAD_9") (pintype "passive"))
      (node (ref "U4") (pin "1") (pinfunction "GND_1") (pintype "passive"))
    )
    (net (code "51") (name "Net-(P2-Pad2)") (class "Default")
      (node (ref "P2") (pin "2") (pinfunction "2_2") (pintype "passive"))
      (node (ref "R7") (pin "2") (pinfunction "2_2") (pintype "passive"))
    )
    (net (code "52") (name "Net-(P2-Pad3)") (class "Default")
      (node (ref "P2") (pin "3") (pinfunction "3_3") (pintype "passive"))
      (node (ref "R11") (pin "2") (pinfunction "2_2") (pintype "passive"))
    )
    (net (code "53") (name "Net-(Q1-D)") (class "Default")
      (node (ref "D1") (pin "1") (pinfunction "1_1") (pintype "passive"))
      (node (ref "Q1") (pin "3") (pinfunction "D_3") (pintype "passive"))
    )
    (net (code "54") (name "Net-(Q1-G)") (class "Default")
      (node (ref "Q1") (pin "1") (pinfunction "G_1") (pintype "passive"))
      (node (ref "R4") (pin "2") (pinfunction "2_2") (pintype "passive"))
      (node (ref "R8") (pin "2") (pinfunction "2_2") (pintype "passive"))
    )
    (net (code "55") (name "Net-(Q2-G)") (class "Default")
      (node (ref "Q2") (pin "1") (pinfunction "G_1") (pintype "passive"))
      (node (ref "R12") (pin "1") (pinfunction "1_1") (pintype "passive"))
      (node (ref "R5") (pin "1") (pinfunction "1_1") (pintype "passive"))
    )
    (net (code "56") (name "Net-(Q3-B)") (class "Default")
      (node (ref "Q3") (pin "1") (pinfunction "B_1") (pintype "passive"))
      (node (ref "R9") (pin "1") (pinfunction "1_1") (pintype "passive"))
    )
    (net (code "57") (name "Net-(Q3-C)") (class "Default")
      (node (ref "Q3") (pin "3") (pinfunction "C_3") (pintype "passive"))
      (node (ref "R5") (pin "2") (pinfunction "2_2") (pintype "passive"))
    )
    (net (code "58") (name "Net-(Q4-B)") (class "Default")
      (node (ref "Q4") (pin "1") (pinfunction "B_1") (pintype "passive"))
      (node (ref "R13") (pin "2") (pinfunction "2_2") (pintype "passive"))
    )
    (net (code "59") (name "Net-(Q4-C)") (class "Default")
      (node (ref "Q4") (pin "3") (pinfunction "C_3") (pintype "passive"))
      (node (ref "R8") (pin "1") (pinfunction "1_1") (pintype "passive"))
    )
    (net (code "60") (name "Net-(Q5-B)") (class "Default")
      (node (ref "Q5") (pin "1") (pinfunction "B_1") (pintype "passive"))
      (node (ref "R16") (pin "1") (pinfunction "1_1") (pintype "passive"))
      (node (ref "R19") (pin "1") (pinfunction "1_1") (pintype "passive"))
    )
    (net (code "61") (name "Net-(Q5-C)") (class "Default")
      (node (ref "Q5") (pin "3") (pinfunction "C_3") (pintype "passive"))
      (node (ref "R17") (pin "1") (pinfunction "1_1") (pintype "passive"))
    )
    (net (code "62") (name "Net-(Q5-E)") (class "Default")
      (node (ref "Q5") (pin "2") (pinfunction "E_2") (pintype "passive"))
      (node (ref "R70") (pin "1") (pinfunction "1_1") (pintype "passive"))
    )
    (net (code "63") (name "Net-(Q6-B)") (class "Default")
      (node (ref "Q6") (pin "1") (pinfunction "B_1") (pintype "passive"))
      (node (ref "R20") (pin "1") (pinfunction "1_1") (pintype "passive"))
      (node (ref "R23") (pin "1") (pinfunction "1_1") (pintype "passive"))
    )
    (net (code "64") (name "Net-(Q6-C)") (class "Default")
      (node (ref "Q6") (pin "3") (pinfunction "C_3") (pintype "passive"))
      (node (ref "R21") (pin "1") (pinfunction "1_1") (pintype "passive"))
    )
    (net (code "65") (name "Net-(Q7-D)") (class "Default")
      (node (ref "D2") (pin "1") (pinfunction "1_1") (pintype "passive"))
      (node (ref "Q7") (pin "3") (pinfunction "D_3") (pintype "passive"))
    )
    (net (code "66") (name "Net-(Q7-G)") (class "Default")
      (node (ref "Q7") (pin "1") (pinfunction "G_1") (pintype "passive"))
      (node (ref "R22") (pin "2") (pinfunction "2_2") (pintype "passive"))
      (node (ref "R26") (pin "2") (pinfunction "2_2") (pintype "passive"))
    )
    (net (code "67") (name "Net-(Q8-B)") (class "Default")
      (node (ref "Q8") (pin "1") (pinfunction "B_1") (pintype "passive"))
      (node (ref "R58") (pin "2") (pinfunction "2_2") (pintype "passive"))
    )
    (net (code "68") (name "Net-(Q8-C)") (class "Default")
      (node (ref "Q8") (pin "3") (pinfunction "C_3") (pintype "passive"))
      (node (ref "R19") (pin "2") (pinfunction "2_2") (pintype "passive"))
    )
    (net (code "69") (name "Net-(Q9-B)") (class "Default")
      (node (ref "Q9") (pin "1") (pinfunction "B_1") (pintype "passive"))
      (node (ref "R57") (pin "2") (pinfunction "2_2") (pintype "passive"))
    )
    (net (code "70") (name "Net-(Q9-C)") (class "Default")
      (node (ref "Q9") (pin "3") (pinfunction "C_3") (pintype "passive"))
      (node (ref "R23") (pin "2") (pinfunction "2_2") (pintype "passive"))
    )
    (net (code "71") (name "Net-(Q10-B)") (class "Default")
      (node (ref "Q10") (pin "1") (pinfunction "B_1") (pintype "passive"))
      (node (ref "R29") (pin "2") (pinfunction "2_2") (pintype "passive"))
    )
    (net (code "72") (name "Net-(Q10-C)") (class "Default")
      (node (ref "Q10") (pin "3") (pinfunction "C_3") (pintype "passive"))
      (node (ref "R26") (pin "1") (pinfunction "1_1") (pintype "passive"))
    )
    (net (code "73") (name "Net-(Q11-B)") (class "Default")
      (node (ref "Q11") (pin "1") (pinfunction "B_1") (pintype "passive"))
      (node (ref "R34") (pin "1") (pinfunction "1_1") (pintype "passive"))
      (node (ref "R36") (pin "1") (pinfunction "1_1") (pintype "passive"))
    )
    (net (code "74") (name "Net-(Q11-C)") (class "Default")
      (node (ref "Q11") (pin "3") (pinfunction "C_3") (pintype "passive"))
      (node (ref "R35") (pin "1") (pinfunction "1_1") (pintype "passive"))
    )
    (net (code "75") (name "Net-(Q12-B)") (class "Default")
      (node (ref "Q12") (pin "1") (pinfunction "B_1") (pintype "passive"))
      (node (ref "R59") (pin "2") (pinfunction "2_2") (pintype "passive"))
    )
    (net (code "76") (name "Net-(Q12-C)") (class "Default")
      (node (ref "Q12") (pin "3") (pinfunction "C_3") (pintype "passive"))
      (node (ref "R36") (pin "2") (pinfunction "2_2") (pintype "passive"))
    )
    (net (code "77") (name "Net-(Q13-B)") (class "Default")
      (node (ref "Q13") (pin "1") (pinfunction "B_1") (pintype "passive"))
      (node (ref "R44") (pin "1") (pinfunction "1_1") (pintype "passive"))
      (node (ref "R46") (pin "1") (pinfunction "1_1") (pintype "passive"))
    )
    (net (code "78") (name "Net-(Q13-C)") (class "Default")
      (node (ref "Q13") (pin "3") (pinfunction "C_3") (pintype "passive"))
      (node (ref "R45") (pin "1") (pinfunction "1_1") (pintype "passive"))
    )
    (net (code "79") (name "Net-(Q13-E)") (class "Default")
      (node (ref "Q13") (pin "2") (pinfunction "E_2") (pintype "passive"))
      (node (ref "R44") (pin "2") (pinfunction "2_2") (pintype "passive"))
      (node (ref "R71") (pin "1") (pinfunction "1_1") (pintype "passive"))
    )
    (net (code "80") (name "Net-(Q14-B)") (class "Default")
      (node (ref "Q14") (pin "1") (pinfunction "B_1") (pintype "passive"))
      (node (ref "R60") (pin "2") (pinfunction "2_2") (pintype "passive"))
    )
    (net (code "81") (name "Net-(Q14-C)") (class "Default")
      (node (ref "Q14") (pin "3") (pinfunction "C_3") (pintype "passive"))
      (node (ref "R46") (pin "2") (pinfunction "2_2") (pintype "passive"))
    )
    (net (code "82") (name "Net-(R40-Pad2)") (class "Default")
      (node (ref "R40") (pin "2") (pinfunction "2_2") (pintype "passive"))
      (node (ref "R41") (pin "1") (pinfunction "1_1") (pintype "passive"))
    )
    (net (code "83") (name "Net-(R49-Pad2)") (class "Default")
      (node (ref "R49") (pin "2") (pinfunction "2_2") (pintype "passive"))
      (node (ref "R50") (pin "1") (pinfunction "1_1") (pintype "passive"))
    )
    (net (code "84") (name "Net-(U1-Vin+)") (class "Default")
      (node (ref "C2") (pin "2") (pinfunction "2_2") (pintype "passive"))
      (node (ref "R10") (pin "2") (pinfunction "2_2") (pintype "passive"))
      (node (ref "U1") (pin "8") (pinfunction "Vin+_8") (pintype "passive"))
    )
    (net (code "85") (name "Net-(U1-Vin-)") (class "Default")
      (node (ref "C2") (pin "1") (pinfunction "1_1") (pintype "passive"))
      (node (ref "R3") (pin "2") (pinfunction "2_2") (pintype "passive"))
      (node (ref "U1") (pin "7") (pinfunction "Vin-_7") (pintype "passive"))
    )
    (net (code "86") (name "Net-(U2-BOOT)") (class "Default")
      (node (ref "C3") (pin "2") (pinfunction "2_2") (pintype "passive"))
      (node (ref "U2") (pin "1") (pinfunction "BOOT_1") (pintype "passive"))
    )
    (net (code "87") (name "Net-(U2-PH)") (class "Default")
      (node (ref "C3") (pin "1") (pinfunction "1_1") (pintype "passive"))
      (node (ref "D3") (pin "2") (pinfunction "2_2") (pintype "passive"))
      (node (ref "L1") (pin "1") (pinfunction "1_1") (pintype "passive"))
      (node (ref "U2") (pin "8") (pinfunction "PH_8") (pintype "passive"))
    )
    (net (code "88") (name "Net-(U2-VSNS)") (class "Default")
      (node (ref "R41") (pin "2") (pinfunction "2_2") (pintype "passive"))
      (node (ref "R42") (pin "1") (pinfunction "1_1") (pintype "passive"))
      (node (ref "U2") (pin "4") (pinfunction "VSNS_4") (pintype "passive"))
    )
    (net (code "89") (name "Net-(U3-BOOT)") (class "Default")
      (node (ref "C7") (pin "2") (pinfunction "2_2") (pintype "passive"))
      (node (ref "U3") (pin "1") (pinfunction "BOOT_1") (pintype "passive"))
    )
    (net (code "90") (name "Net-(U3-PH)") (class "Default")
      (node (ref "C7") (pin "1") (pinfunction "1_1") (pintype "passive"))
      (node (ref "D4") (pin "2") (pinfunction "2_2") (pintype "passive"))
      (node (ref "L2") (pin "1") (pinfunction "1_1") (pintype "passive"))
      (node (ref "U3") (pin "8") (pinfunction "PH_8") (pintype "passive"))
    )
    (net (code "91") (name "Net-(U3-VSNS)") (class "Default")
      (node (ref "R50") (pin "2") (pinfunction "2_2") (pintype "passive"))
      (node (ref "R51") (pin "1") (pinfunction "1_1") (pintype "passive"))
      (node (ref "U3") (pin "4") (pinfunction "VSNS_4") (pintype "passive"))
    )
    (net (code "92") (name "VIN_5V") (class "Default")
      (node (ref "C10") (pin "1") (pinfunction "1_1") (pintype "passive"))
      (node (ref "C12") (pin "1") (pinfunction "1_1") (pintype "passive"))
      (node (ref "L2") (pin "2") (pinfunction "2_2") (pintype "passive"))
      (node (ref "R48") (pin "2") (pinfunction "2_2") (pintype "passive"))
      (node (ref "R51") (pin "2") (pinfunction "2_2") (pintype "passive"))
      (node (ref "U4") (pin "2") (pinfunction "Vin_2") (pintype "passive"))
    )
    (net (code "93") (name "VIN_12V") (class "Default")
      (node (ref "C4") (pin "1") (pinfunction "1_1") (pintype "passive"))
      (node (ref "C5") (pin "1") (pinfunction "1_1") (pintype "passive"))
      (node (ref "C8") (pin "1") (pinfunction "1_1") (pintype "passive"))
      (node (ref "C9") (pin "1") (pinfunction "1_1") (pintype "passive"))
      (node (ref "JP1") (pin "1") (pinfunction "1_1") (pintype "passive"))
      (node (ref "JP2") (pin "1") (pinfunction "1_1") (pintype "passive"))
      (node (ref "U2") (pin "7") (pinfunction "VIN_7") (pintype "passive"))
      (node (ref "U3") (pin "7") (pinfunction "VIN_7") (pintype "passive"))
    )
    (net (code "94") (name "unconnected-(J1-Pad13)") (class "Default")
      (node (ref "J1") (pin "13") (pinfunction "13_13") (pintype "passive"))
    )
    (net (code "95") (name "unconnected-(J1-Pad16)") (class "Default")
      (node (ref "J1") (pin "16") (pinfunction "16_16") (pintype "passive"))
    )
    (net (code "96") (name "unconnected-(J1-Pad18)") (class "Default")
      (node (ref "J1") (pin "18") (pinfunction "18_18") (pintype "passive"))
    )
    (net (code "97") (name "unconnected-(J1-Pad20)") (class "Default")
      (node (ref "J1") (pin "20") (pinfunction "20_20") (pintype "passive"))
    )
    (net (code "98") (name "unconnected-(P1-Pad1)") (class "Default")
      (node (ref "P1") (pin "1") (pinfunction "1_1") (pintype "passive"))
    )
    (net (code "99") (name "unconnected-(P2-Pad1)") (class "Default")
      (node (ref "P2") (pin "1") (pinfunction "1_1") (pintype "passive"))
    )
    (net (code "100") (name "unconnected-(R16-Pad2)") (class "Default")
      (node (ref "R16") (pin "2") (pinfunction "2_2") (pintype "passive"))
    )
    (net (code "101") (name "unconnected-(U2-ENA-Pad5)") (class "Default")
      (node (ref "U2") (pin "5") (pinfunction "ENA_5") (pintype "passive"))
    )
    (net (code "102") (name "unconnected-(U2-NC-Pad2)") (class "Default")
      (node (ref "U2") (pin "2") (pinfunction "NC_2") (pintype "passive"))
    )
    (net (code "103") (name "unconnected-(U2-NC-Pad3)") (class "Default")
      (node (ref "U2") (pin "3") (pinfunction "NC_3") (pintype "passive"))
    )
    (net (code "104") (name "unconnected-(U3-ENA-Pad5)") (class "Default")
      (node (ref "U3") (pin "5") (pinfunction "ENA_5") (pintype "passive"))
    )
    (net (code "105") (name "unconnected-(U3-NC-Pad2)") (class "Default")
      (node (ref "U3") (pin "2") (pinfunction "NC_2") (pintype "passive"))
    )
    (net (code "106") (name "unconnected-(U3-NC-Pad3)") (class "Default")
      (node (ref "U3") (pin "3") (pinfunction "NC_3") (pintype "passive"))
    )
  )
)
